# SpiderHand.net
KiCad netlist of a schematic drawn in EAGLE
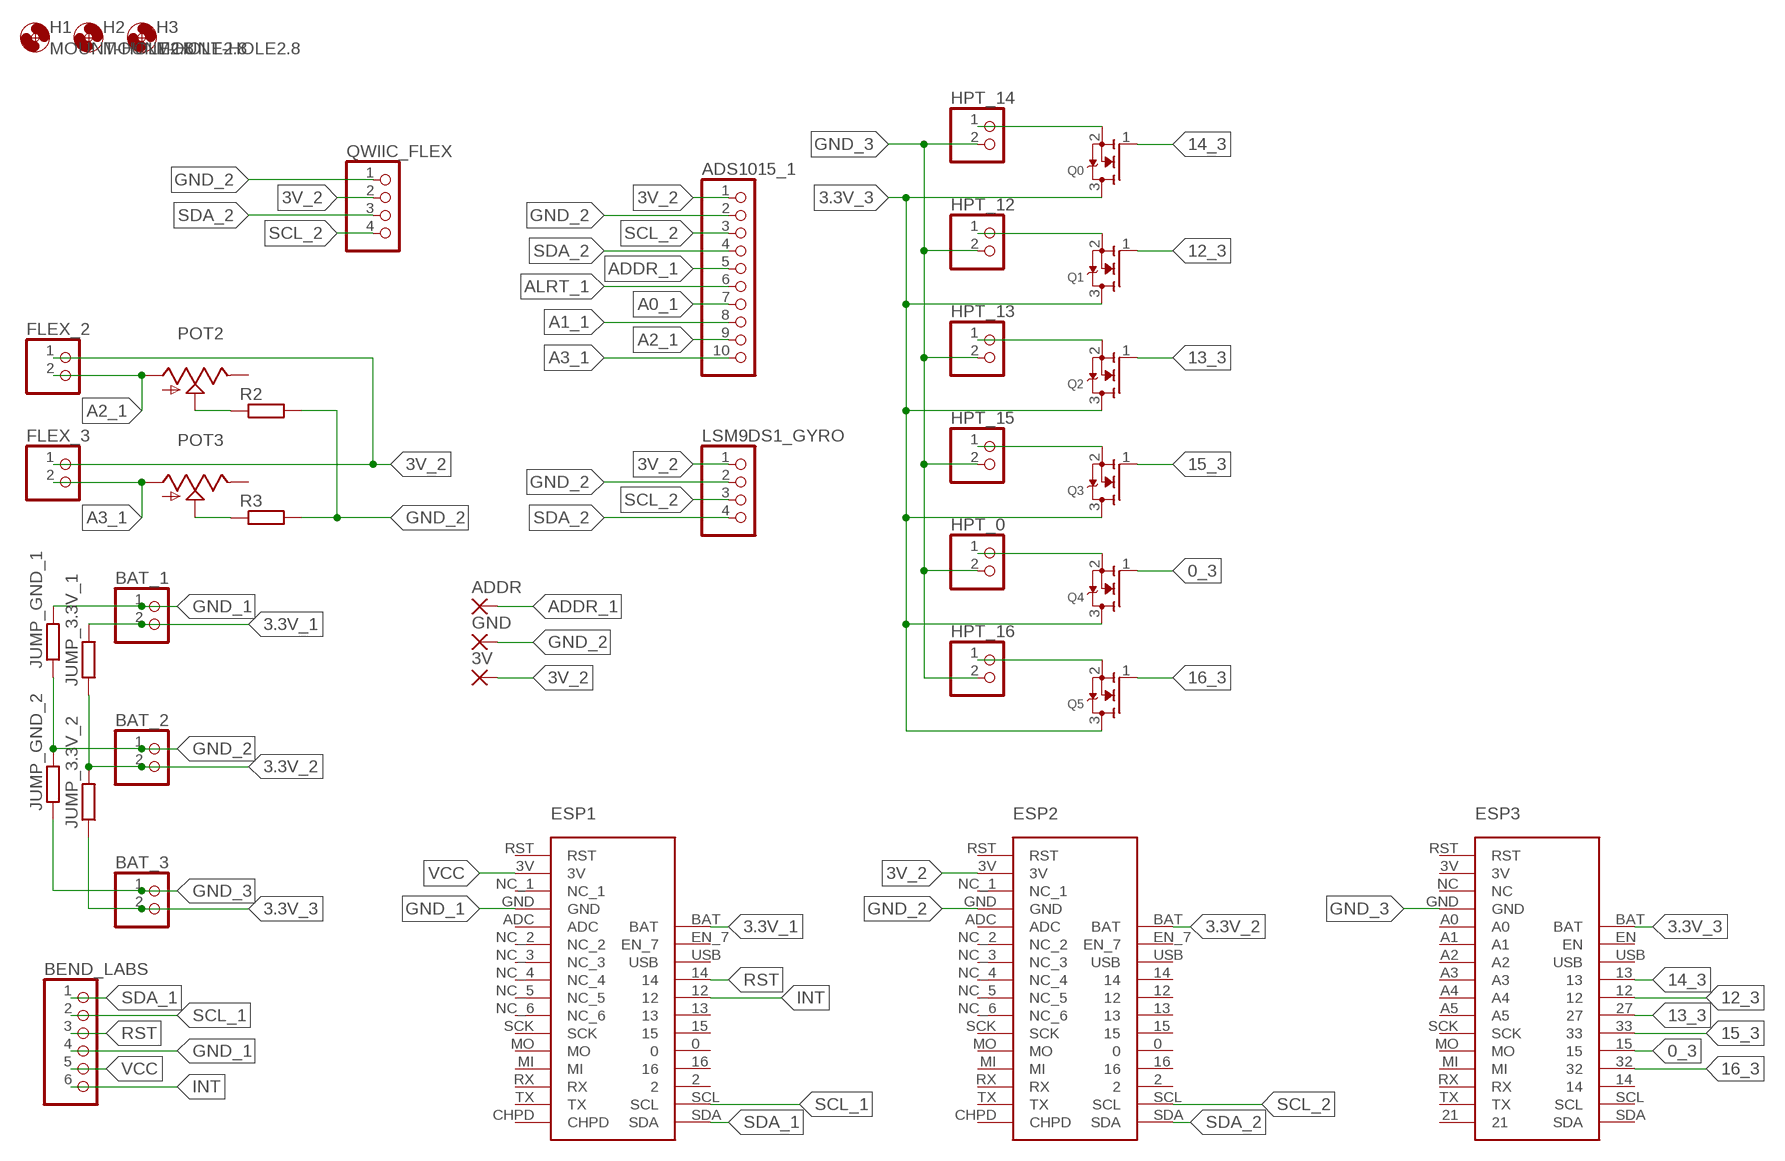
[diagram p0: schematic, sheet 1]

(export (version "E")
  (design (tool "Eeschema 10.0.6"))
  (components
    (comp (ref "3V")
      (value "SMD2")
      (footprint "eagle-import:SMD1,27-2,54")
      (libsource (lib "eagle-import") (part "SMD2"))
    )
    (comp (ref "ADDR")
      (value "SMD2")
      (footprint "eagle-import:SMD1,27-2,54")
      (libsource (lib "eagle-import") (part "SMD2"))
    )
    (comp (ref "ADS1015_1")
      (value "PINHD-1X10")
      (footprint "eagle-import:1X10")
      (libsource (lib "eagle-import") (part "PINHD-1X10"))
    )
    (comp (ref "BAT_1")
      (value "PINHD-1X2")
      (footprint "eagle-import:1X02")
      (libsource (lib "eagle-import") (part "PINHD-1X2"))
    )
    (comp (ref "BAT_2")
      (value "PINHD-1X2")
      (footprint "eagle-import:1X02")
      (libsource (lib "eagle-import") (part "PINHD-1X2"))
    )
    (comp (ref "BAT_3")
      (value "PINHD-1X2")
      (footprint "eagle-import:1X02")
      (fields (field (name "SPICEPREFIX") "B"))
      (libsource (lib "eagle-import") (part "PINHD-1X2"))
    )
    (comp (ref "BEND_LABS")
      (value "PINHD-1X6/90")
      (footprint "eagle-import:1X06_90")
      (libsource (lib "eagle-import") (part "PINHD-1X6/90"))
    )
    (comp (ref "ESP1")
      (value "ESP_8266_ADAFRUIT")
      (footprint "eagle-import:ESP_8266_ADAFRUIT")
      (libsource (lib "eagle-import") (part "ESP_8266_ADAFRUIT"))
    )
    (comp (ref "ESP2")
      (value "ESP_8266_ADAFRUIT")
      (footprint "eagle-import:ESP_8266_ADAFRUIT")
      (libsource (lib "eagle-import") (part "ESP_8266_ADAFRUIT"))
    )
    (comp (ref "ESP3")
      (value "ESP_32_ADAFRUIT")
      (footprint "eagle-import:ESP_32_ADAFRUIT")
      (libsource (lib "eagle-import") (part "ESP_32_ADAFRUIT"))
    )
    (comp (ref "FLEX_2")
      (value "PINHD-1X2")
      (footprint "eagle-import:1X02")
      (libsource (lib "eagle-import") (part "PINHD-1X2"))
    )
    (comp (ref "FLEX_3")
      (value "PINHD-1X2")
      (footprint "eagle-import:1X02")
      (libsource (lib "eagle-import") (part "PINHD-1X2"))
    )
    (comp (ref "GND")
      (value "SMD2")
      (footprint "eagle-import:SMD1,27-2,54")
      (libsource (lib "eagle-import") (part "SMD2"))
    )
    (comp (ref "H1")
      (value "MOUNT-HOLE2.8")
      (footprint "eagle-import:2,8")
      (libsource (lib "eagle-import") (part "MOUNT-HOLE2.8"))
    )
    (comp (ref "H2")
      (value "MOUNT-HOLE2.8")
      (footprint "eagle-import:2,8")
      (libsource (lib "eagle-import") (part "MOUNT-HOLE2.8"))
    )
    (comp (ref "H3")
      (value "MOUNT-HOLE2.8")
      (footprint "eagle-import:2,8")
      (libsource (lib "eagle-import") (part "MOUNT-HOLE2.8"))
    )
    (comp (ref "HPT_0")
      (value "PINHD-1X2")
      (footprint "eagle-import:1X02")
      (libsource (lib "eagle-import") (part "PINHD-1X2"))
    )
    (comp (ref "HPT_12")
      (value "PINHD-1X2")
      (footprint "eagle-import:1X02")
      (libsource (lib "eagle-import") (part "PINHD-1X2"))
    )
    (comp (ref "HPT_13")
      (value "PINHD-1X2")
      (footprint "eagle-import:1X02")
      (libsource (lib "eagle-import") (part "PINHD-1X2"))
    )
    (comp (ref "HPT_14")
      (value "PINHD-1X2")
      (footprint "eagle-import:1X02")
      (libsource (lib "eagle-import") (part "PINHD-1X2"))
    )
    (comp (ref "HPT_15")
      (value "PINHD-1X2")
      (footprint "eagle-import:1X02")
      (libsource (lib "eagle-import") (part "PINHD-1X2"))
    )
    (comp (ref "HPT_16")
      (value "PINHD-1X2")
      (footprint "eagle-import:1X02")
      (libsource (lib "eagle-import") (part "PINHD-1X2"))
    )
    (comp (ref "JUMP_3.3V_1")
      (value "R-EU_M0805")
      (footprint "eagle-import:M0805")
      (libsource (lib "eagle-import") (part "R-EU_M0805"))
    )
    (comp (ref "JUMP_3.3V_2")
      (value "R-EU_M0805")
      (footprint "eagle-import:M0805")
      (libsource (lib "eagle-import") (part "R-EU_M0805"))
    )
    (comp (ref "JUMP_GND_1")
      (value "R-EU_M0805")
      (footprint "eagle-import:M0805")
      (libsource (lib "eagle-import") (part "R-EU_M0805"))
    )
    (comp (ref "JUMP_GND_2")
      (value "R-EU_M0805")
      (footprint "eagle-import:M0805")
      (libsource (lib "eagle-import") (part "R-EU_M0805"))
    )
    (comp (ref "LSM9DS1_GYRO")
      (value "PINHD-1X4/90")
      (footprint "eagle-import:1X04_90")
      (libsource (lib "eagle-import") (part "PINHD-1X4/90"))
    )
    (comp (ref "POT2")
      (value "TRIM_US-CA6V")
      (footprint "eagle-import:CA6V")
      (libsource (lib "eagle-import") (part "TRIM_US-CA6V"))
    )
    (comp (ref "POT3")
      (value "TRIM_US-CA6V")
      (footprint "eagle-import:CA6V")
      (libsource (lib "eagle-import") (part "TRIM_US-CA6V"))
    )
    (comp (ref "Q0")
      (value "MOSFET-NREFLOW")
      (footprint "eagle-import:SOT23")
      (libsource (lib "eagle-import") (part "MOSFET-NREFLOW"))
    )
    (comp (ref "Q1")
      (value "MOSFET-NREFLOW")
      (footprint "eagle-import:SOT23")
      (libsource (lib "eagle-import") (part "MOSFET-NREFLOW"))
    )
    (comp (ref "Q2")
      (value "MOSFET-NREFLOW")
      (footprint "eagle-import:SOT23")
      (libsource (lib "eagle-import") (part "MOSFET-NREFLOW"))
    )
    (comp (ref "Q3")
      (value "MOSFET-NREFLOW")
      (footprint "eagle-import:SOT23")
      (libsource (lib "eagle-import") (part "MOSFET-NREFLOW"))
    )
    (comp (ref "Q4")
      (value "MOSFET-NREFLOW")
      (footprint "eagle-import:SOT23")
      (libsource (lib "eagle-import") (part "MOSFET-NREFLOW"))
    )
    (comp (ref "Q5")
      (value "MOSFET-NREFLOW")
      (footprint "eagle-import:SOT23")
      (libsource (lib "eagle-import") (part "MOSFET-NREFLOW"))
    )
    (comp (ref "QWIIC_FLEX")
      (value "PINHD-1X4/90")
      (footprint "eagle-import:1X04_90")
      (libsource (lib "eagle-import") (part "PINHD-1X4/90"))
    )
    (comp (ref "R2")
      (value "R-EU_0204/7")
      (footprint "eagle-import:0204_7")
      (libsource (lib "eagle-import") (part "R-EU_0204/7"))
    )
    (comp (ref "R3")
      (value "R-EU_0204/7")
      (footprint "eagle-import:0204_7")
      (libsource (lib "eagle-import") (part "R-EU_0204/7"))
    )
  )
  (nets
    (net (code "1") (name "0_3") (class "Default")
      (node (ref "ESP3") (pin "15") (pinfunction "15_15") (pintype "bidirectional"))
      (node (ref "Q4") (pin "1") (pinfunction "G_1") (pintype "bidirectional"))
    )
    (net (code "2") (name "3.3V_1") (class "Default")
      (node (ref "BAT_1") (pin "2") (pinfunction "2_2") (pintype "passive"))
      (node (ref "ESP1") (pin "BAT") (pinfunction "BAT_BAT") (pintype "bidirectional"))
      (node (ref "JUMP_3.3V_1") (pin "2") (pinfunction "2_2") (pintype "passive"))
    )
    (net (code "3") (name "3.3V_2") (class "Default")
      (node (ref "BAT_2") (pin "2") (pinfunction "2_2") (pintype "passive"))
      (node (ref "ESP2") (pin "BAT") (pinfunction "BAT_BAT") (pintype "bidirectional"))
      (node (ref "JUMP_3.3V_1") (pin "1") (pinfunction "1_1") (pintype "passive"))
      (node (ref "JUMP_3.3V_2") (pin "2") (pinfunction "2_2") (pintype "passive"))
    )
    (net (code "4") (name "3.3V_3") (class "Default")
      (node (ref "BAT_3") (pin "2") (pinfunction "2_2") (pintype "passive"))
      (node (ref "ESP3") (pin "BAT") (pinfunction "BAT_BAT") (pintype "bidirectional"))
      (node (ref "JUMP_3.3V_2") (pin "1") (pinfunction "1_1") (pintype "passive"))
      (node (ref "Q0") (pin "3") (pinfunction "D_3") (pintype "bidirectional"))
      (node (ref "Q1") (pin "3") (pinfunction "D_3") (pintype "bidirectional"))
      (node (ref "Q2") (pin "3") (pinfunction "D_3") (pintype "bidirectional"))
      (node (ref "Q3") (pin "3") (pinfunction "D_3") (pintype "bidirectional"))
      (node (ref "Q4") (pin "3") (pinfunction "D_3") (pintype "bidirectional"))
      (node (ref "Q5") (pin "3") (pinfunction "D_3") (pintype "bidirectional"))
    )
    (net (code "5") (name "3V_2") (class "Default")
      (node (ref "3V") (pin "1") (pinfunction "P_1") (pintype "passive"))
      (node (ref "ADS1015_1") (pin "1") (pinfunction "1_1") (pintype "passive"))
      (node (ref "ESP2") (pin "3V") (pinfunction "3V_3V") (pintype "bidirectional"))
      (node (ref "FLEX_2") (pin "1") (pinfunction "1_1") (pintype "passive"))
      (node (ref "FLEX_3") (pin "1") (pinfunction "1_1") (pintype "passive"))
      (node (ref "LSM9DS1_GYRO") (pin "1") (pinfunction "1_1") (pintype "passive"))
      (node (ref "QWIIC_FLEX") (pin "2") (pinfunction "2_2") (pintype "passive"))
    )
    (net (code "6") (name "12_3") (class "Default")
      (node (ref "ESP3") (pin "12") (pinfunction "12_12") (pintype "bidirectional"))
      (node (ref "Q1") (pin "1") (pinfunction "G_1") (pintype "bidirectional"))
    )
    (net (code "7") (name "13_3") (class "Default")
      (node (ref "ESP3") (pin "27") (pinfunction "27_27") (pintype "bidirectional"))
      (node (ref "Q2") (pin "1") (pinfunction "G_1") (pintype "bidirectional"))
    )
    (net (code "8") (name "14_3") (class "Default")
      (node (ref "ESP3") (pin "13") (pinfunction "13_13") (pintype "bidirectional"))
      (node (ref "Q0") (pin "1") (pinfunction "G_1") (pintype "bidirectional"))
    )
    (net (code "9") (name "15_3") (class "Default")
      (node (ref "ESP3") (pin "33") (pinfunction "33_33") (pintype "bidirectional"))
      (node (ref "Q3") (pin "1") (pinfunction "G_1") (pintype "bidirectional"))
    )
    (net (code "10") (name "16_3") (class "Default")
      (node (ref "ESP3") (pin "32") (pinfunction "32_32") (pintype "bidirectional"))
      (node (ref "Q5") (pin "1") (pinfunction "G_1") (pintype "bidirectional"))
    )
    (net (code "11") (name "A0_1") (class "Default")
      (node (ref "ADS1015_1") (pin "7") (pinfunction "7_7") (pintype "passive"))
    )
    (net (code "12") (name "A1_1") (class "Default")
      (node (ref "ADS1015_1") (pin "8") (pinfunction "8_8") (pintype "passive"))
    )
    (net (code "13") (name "A2_1") (class "Default")
      (node (ref "ADS1015_1") (pin "9") (pinfunction "9_9") (pintype "passive"))
      (node (ref "FLEX_2") (pin "2") (pinfunction "2_2") (pintype "passive"))
      (node (ref "POT2") (pin "A") (pinfunction "A_A") (pintype "passive"))
    )
    (net (code "14") (name "A3_1") (class "Default")
      (node (ref "ADS1015_1") (pin "10") (pinfunction "10_10") (pintype "passive"))
      (node (ref "FLEX_3") (pin "2") (pinfunction "2_2") (pintype "passive"))
      (node (ref "POT3") (pin "A") (pinfunction "A_A") (pintype "passive"))
    )
    (net (code "15") (name "ADDR_1") (class "Default")
      (node (ref "ADDR") (pin "1") (pinfunction "P_1") (pintype "passive"))
      (node (ref "ADS1015_1") (pin "5") (pinfunction "5_5") (pintype "passive"))
    )
    (net (code "16") (name "ALRT_1") (class "Default")
      (node (ref "ADS1015_1") (pin "6") (pinfunction "6_6") (pintype "passive"))
    )
    (net (code "17") (name "GND_1") (class "Default")
      (node (ref "BAT_1") (pin "1") (pinfunction "1_1") (pintype "passive"))
      (node (ref "BEND_LABS") (pin "4") (pinfunction "4_4") (pintype "passive"))
      (node (ref "ESP1") (pin "GND") (pinfunction "GND_GND") (pintype "bidirectional"))
      (node (ref "JUMP_GND_1") (pin "2") (pinfunction "2_2") (pintype "passive"))
    )
    (net (code "18") (name "GND_2") (class "Default")
      (node (ref "ADS1015_1") (pin "2") (pinfunction "2_2") (pintype "passive"))
      (node (ref "BAT_2") (pin "1") (pinfunction "1_1") (pintype "passive"))
      (node (ref "ESP2") (pin "GND") (pinfunction "GND_GND") (pintype "bidirectional"))
      (node (ref "GND") (pin "1") (pinfunction "P_1") (pintype "passive"))
      (node (ref "JUMP_GND_1") (pin "1") (pinfunction "1_1") (pintype "passive"))
      (node (ref "JUMP_GND_2") (pin "2") (pinfunction "2_2") (pintype "passive"))
      (node (ref "LSM9DS1_GYRO") (pin "2") (pinfunction "2_2") (pintype "passive"))
      (node (ref "QWIIC_FLEX") (pin "1") (pinfunction "1_1") (pintype "passive"))
      (node (ref "R2") (pin "2") (pinfunction "2_2") (pintype "passive"))
      (node (ref "R3") (pin "2") (pinfunction "2_2") (pintype "passive"))
    )
    (net (code "19") (name "GND_3") (class "Default")
      (node (ref "BAT_3") (pin "1") (pinfunction "1_1") (pintype "passive"))
      (node (ref "ESP3") (pin "GND") (pinfunction "GND_GND") (pintype "bidirectional"))
      (node (ref "HPT_0") (pin "2") (pinfunction "2_2") (pintype "passive"))
      (node (ref "HPT_12") (pin "2") (pinfunction "2_2") (pintype "passive"))
      (node (ref "HPT_13") (pin "2") (pinfunction "2_2") (pintype "passive"))
      (node (ref "HPT_14") (pin "2") (pinfunction "2_2") (pintype "passive"))
      (node (ref "HPT_15") (pin "2") (pinfunction "2_2") (pintype "passive"))
      (node (ref "HPT_16") (pin "2") (pinfunction "2_2") (pintype "passive"))
      (node (ref "JUMP_GND_2") (pin "1") (pinfunction "1_1") (pintype "passive"))
    )
    (net (code "20") (name "INT") (class "Default")
      (node (ref "BEND_LABS") (pin "6") (pinfunction "6_6") (pintype "passive"))
      (node (ref "ESP1") (pin "12") (pinfunction "12_12") (pintype "bidirectional"))
    )
    (net (code "21") (name "Net-(POT2-PadS)") (class "Default")
      (node (ref "POT2") (pin "S") (pinfunction "S_S") (pintype "passive"))
      (node (ref "R2") (pin "1") (pinfunction "1_1") (pintype "passive"))
    )
    (net (code "22") (name "Net-(POT3-PadS)") (class "Default")
      (node (ref "POT3") (pin "S") (pinfunction "S_S") (pintype "passive"))
      (node (ref "R3") (pin "1") (pinfunction "1_1") (pintype "passive"))
    )
    (net (code "23") (name "Net-(Q0-S)") (class "Default")
      (node (ref "HPT_14") (pin "1") (pinfunction "1_1") (pintype "passive"))
      (node (ref "Q0") (pin "2") (pinfunction "S_2") (pintype "bidirectional"))
    )
    (net (code "24") (name "Net-(Q1-S)") (class "Default")
      (node (ref "HPT_12") (pin "1") (pinfunction "1_1") (pintype "passive"))
      (node (ref "Q1") (pin "2") (pinfunction "S_2") (pintype "bidirectional"))
    )
    (net (code "25") (name "Net-(Q2-S)") (class "Default")
      (node (ref "HPT_13") (pin "1") (pinfunction "1_1") (pintype "passive"))
      (node (ref "Q2") (pin "2") (pinfunction "S_2") (pintype "bidirectional"))
    )
    (net (code "26") (name "Net-(Q3-S)") (class "Default")
      (node (ref "HPT_15") (pin "1") (pinfunction "1_1") (pintype "passive"))
      (node (ref "Q3") (pin "2") (pinfunction "S_2") (pintype "bidirectional"))
    )
    (net (code "27") (name "Net-(Q4-S)") (class "Default")
      (node (ref "HPT_0") (pin "1") (pinfunction "1_1") (pintype "passive"))
      (node (ref "Q4") (pin "2") (pinfunction "S_2") (pintype "bidirectional"))
    )
    (net (code "28") (name "Net-(Q5-S)") (class "Default")
      (node (ref "HPT_16") (pin "1") (pinfunction "1_1") (pintype "passive"))
      (node (ref "Q5") (pin "2") (pinfunction "S_2") (pintype "bidirectional"))
    )
    (net (code "29") (name "RST") (class "Default")
      (node (ref "BEND_LABS") (pin "3") (pinfunction "3_3") (pintype "passive"))
      (node (ref "ESP1") (pin "14") (pinfunction "14_14") (pintype "bidirectional"))
    )
    (net (code "30") (name "SCL_1") (class "Default")
      (node (ref "BEND_LABS") (pin "2") (pinfunction "2_2") (pintype "passive"))
      (node (ref "ESP1") (pin "SCL") (pinfunction "SCL_SCL") (pintype "bidirectional"))
    )
    (net (code "31") (name "SCL_2") (class "Default")
      (node (ref "ADS1015_1") (pin "3") (pinfunction "3_3") (pintype "passive"))
      (node (ref "ESP2") (pin "SCL") (pinfunction "SCL_SCL") (pintype "bidirectional"))
      (node (ref "LSM9DS1_GYRO") (pin "3") (pinfunction "3_3") (pintype "passive"))
      (node (ref "QWIIC_FLEX") (pin "4") (pinfunction "4_4") (pintype "passive"))
    )
    (net (code "32") (name "SDA_1") (class "Default")
      (node (ref "BEND_LABS") (pin "1") (pinfunction "1_1") (pintype "passive"))
      (node (ref "ESP1") (pin "SDA") (pinfunction "SDA_SDA") (pintype "bidirectional"))
    )
    (net (code "33") (name "SDA_2") (class "Default")
      (node (ref "ADS1015_1") (pin "4") (pinfunction "4_4") (pintype "passive"))
      (node (ref "ESP2") (pin "SDA") (pinfunction "SDA_SDA") (pintype "bidirectional"))
      (node (ref "LSM9DS1_GYRO") (pin "4") (pinfunction "4_4") (pintype "passive"))
      (node (ref "QWIIC_FLEX") (pin "3") (pinfunction "3_3") (pintype "passive"))
    )
    (net (code "34") (name "VCC") (class "Default")
      (node (ref "BEND_LABS") (pin "5") (pinfunction "5_5") (pintype "passive"))
      (node (ref "ESP1") (pin "3V") (pinfunction "3V_3V") (pintype "bidirectional"))
    )
    (net (code "35") (name "unconnected-(ESP1-Pad0)") (class "Default")
      (node (ref "ESP1") (pin "0") (pinfunction "0_0") (pintype "bidirectional"))
    )
    (net (code "36") (name "unconnected-(ESP1-Pad2)") (class "Default")
      (node (ref "ESP1") (pin "2") (pinfunction "2_2") (pintype "bidirectional"))
    )
    (net (code "37") (name "unconnected-(ESP1-Pad13)") (class "Default")
      (node (ref "ESP1") (pin "13") (pinfunction "13_13") (pintype "bidirectional"))
    )
    (net (code "38") (name "unconnected-(ESP1-Pad15)") (class "Default")
      (node (ref "ESP1") (pin "15") (pinfunction "15_15") (pintype "bidirectional"))
    )
    (net (code "39") (name "unconnected-(ESP1-Pad16)") (class "Default")
      (node (ref "ESP1") (pin "16") (pinfunction "16_16") (pintype "bidirectional"))
    )
    (net (code "40") (name "unconnected-(ESP1-PadADC)") (class "Default")
      (node (ref "ESP1") (pin "ADC") (pinfunction "ADC_ADC") (pintype "bidirectional"))
    )
    (net (code "41") (name "unconnected-(ESP1-PadCHPD)") (class "Default")
      (node (ref "ESP1") (pin "CHPD") (pinfunction "CHPD_CHPD") (pintype "bidirectional"))
    )
    (net (code "42") (name "unconnected-(ESP1-PadEN_7)") (class "Default")
      (node (ref "ESP1") (pin "EN_7") (pinfunction "EN_7_EN_7") (pintype "bidirectional"))
    )
    (net (code "43") (name "unconnected-(ESP1-PadMI)") (class "Default")
      (node (ref "ESP1") (pin "MI") (pinfunction "MI_MI") (pintype "bidirectional"))
    )
    (net (code "44") (name "unconnected-(ESP1-PadMO)") (class "Default")
      (node (ref "ESP1") (pin "MO") (pinfunction "MO_MO") (pintype "bidirectional"))
    )
    (net (code "45") (name "unconnected-(ESP1-PadNC_1)") (class "Default")
      (node (ref "ESP1") (pin "NC_1") (pinfunction "NC_1_NC_1") (pintype "bidirectional"))
    )
    (net (code "46") (name "unconnected-(ESP1-PadNC_2)") (class "Default")
      (node (ref "ESP1") (pin "NC_2") (pinfunction "NC_2_NC_2") (pintype "bidirectional"))
    )
    (net (code "47") (name "unconnected-(ESP1-PadNC_3)") (class "Default")
      (node (ref "ESP1") (pin "NC_3") (pinfunction "NC_3_NC_3") (pintype "bidirectional"))
    )
    (net (code "48") (name "unconnected-(ESP1-PadNC_4)") (class "Default")
      (node (ref "ESP1") (pin "NC_4") (pinfunction "NC_4_NC_4") (pintype "bidirectional"))
    )
    (net (code "49") (name "unconnected-(ESP1-PadNC_5)") (class "Default")
      (node (ref "ESP1") (pin "NC_5") (pinfunction "NC_5_NC_5") (pintype "bidirectional"))
    )
    (net (code "50") (name "unconnected-(ESP1-PadNC_6)") (class "Default")
      (node (ref "ESP1") (pin "NC_6") (pinfunction "NC_6_NC_6") (pintype "bidirectional"))
    )
    (net (code "51") (name "unconnected-(ESP1-PadRST)") (class "Default")
      (node (ref "ESP1") (pin "RST") (pinfunction "RST_RST") (pintype "bidirectional"))
    )
    (net (code "52") (name "unconnected-(ESP1-PadRX)") (class "Default")
      (node (ref "ESP1") (pin "RX") (pinfunction "RX_RX") (pintype "bidirectional"))
    )
    (net (code "53") (name "unconnected-(ESP1-PadSCK)") (class "Default")
      (node (ref "ESP1") (pin "SCK") (pinfunction "SCK_SCK") (pintype "bidirectional"))
    )
    (net (code "54") (name "unconnected-(ESP1-PadTX)") (class "Default")
      (node (ref "ESP1") (pin "TX") (pinfunction "TX_TX") (pintype "bidirectional"))
    )
    (net (code "55") (name "unconnected-(ESP1-PadUSB)") (class "Default")
      (node (ref "ESP1") (pin "USB") (pinfunction "USB_USB") (pintype "bidirectional"))
    )
    (net (code "56") (name "unconnected-(ESP2-Pad0)") (class "Default")
      (node (ref "ESP2") (pin "0") (pinfunction "0_0") (pintype "bidirectional"))
    )
    (net (code "57") (name "unconnected-(ESP2-Pad2)") (class "Default")
      (node (ref "ESP2") (pin "2") (pinfunction "2_2") (pintype "bidirectional"))
    )
    (net (code "58") (name "unconnected-(ESP2-Pad12)") (class "Default")
      (node (ref "ESP2") (pin "12") (pinfunction "12_12") (pintype "bidirectional"))
    )
    (net (code "59") (name "unconnected-(ESP2-Pad13)") (class "Default")
      (node (ref "ESP2") (pin "13") (pinfunction "13_13") (pintype "bidirectional"))
    )
    (net (code "60") (name "unconnected-(ESP2-Pad14)") (class "Default")
      (node (ref "ESP2") (pin "14") (pinfunction "14_14") (pintype "bidirectional"))
    )
    (net (code "61") (name "unconnected-(ESP2-Pad15)") (class "Default")
      (node (ref "ESP2") (pin "15") (pinfunction "15_15") (pintype "bidirectional"))
    )
    (net (code "62") (name "unconnected-(ESP2-Pad16)") (class "Default")
      (node (ref "ESP2") (pin "16") (pinfunction "16_16") (pintype "bidirectional"))
    )
    (net (code "63") (name "unconnected-(ESP2-PadADC)") (class "Default")
      (node (ref "ESP2") (pin "ADC") (pinfunction "ADC_ADC") (pintype "bidirectional"))
    )
    (net (code "64") (name "unconnected-(ESP2-PadCHPD)") (class "Default")
      (node (ref "ESP2") (pin "CHPD") (pinfunction "CHPD_CHPD") (pintype "bidirectional"))
    )
    (net (code "65") (name "unconnected-(ESP2-PadEN_7)") (class "Default")
      (node (ref "ESP2") (pin "EN_7") (pinfunction "EN_7_EN_7") (pintype "bidirectional"))
    )
    (net (code "66") (name "unconnected-(ESP2-PadMI)") (class "Default")
      (node (ref "ESP2") (pin "MI") (pinfunction "MI_MI") (pintype "bidirectional"))
    )
    (net (code "67") (name "unconnected-(ESP2-PadMO)") (class "Default")
      (node (ref "ESP2") (pin "MO") (pinfunction "MO_MO") (pintype "bidirectional"))
    )
    (net (code "68") (name "unconnected-(ESP2-PadNC_1)") (class "Default")
      (node (ref "ESP2") (pin "NC_1") (pinfunction "NC_1_NC_1") (pintype "bidirectional"))
    )
    (net (code "69") (name "unconnected-(ESP2-PadNC_2)") (class "Default")
      (node (ref "ESP2") (pin "NC_2") (pinfunction "NC_2_NC_2") (pintype "bidirectional"))
    )
    (net (code "70") (name "unconnected-(ESP2-PadNC_3)") (class "Default")
      (node (ref "ESP2") (pin "NC_3") (pinfunction "NC_3_NC_3") (pintype "bidirectional"))
    )
    (net (code "71") (name "unconnected-(ESP2-PadNC_4)") (class "Default")
      (node (ref "ESP2") (pin "NC_4") (pinfunction "NC_4_NC_4") (pintype "bidirectional"))
    )
    (net (code "72") (name "unconnected-(ESP2-PadNC_5)") (class "Default")
      (node (ref "ESP2") (pin "NC_5") (pinfunction "NC_5_NC_5") (pintype "bidirectional"))
    )
    (net (code "73") (name "unconnected-(ESP2-PadNC_6)") (class "Default")
      (node (ref "ESP2") (pin "NC_6") (pinfunction "NC_6_NC_6") (pintype "bidirectional"))
    )
    (net (code "74") (name "unconnected-(ESP2-PadRST)") (class "Default")
      (node (ref "ESP2") (pin "RST") (pinfunction "RST_RST") (pintype "bidirectional"))
    )
    (net (code "75") (name "unconnected-(ESP2-PadRX)") (class "Default")
      (node (ref "ESP2") (pin "RX") (pinfunction "RX_RX") (pintype "bidirectional"))
    )
    (net (code "76") (name "unconnected-(ESP2-PadSCK)") (class "Default")
      (node (ref "ESP2") (pin "SCK") (pinfunction "SCK_SCK") (pintype "bidirectional"))
    )
    (net (code "77") (name "unconnected-(ESP2-PadTX)") (class "Default")
      (node (ref "ESP2") (pin "TX") (pinfunction "TX_TX") (pintype "bidirectional"))
    )
    (net (code "78") (name "unconnected-(ESP2-PadUSB)") (class "Default")
      (node (ref "ESP2") (pin "USB") (pinfunction "USB_USB") (pintype "bidirectional"))
    )
    (net (code "79") (name "unconnected-(ESP3-Pad3V)") (class "Default")
      (node (ref "ESP3") (pin "3V") (pinfunction "3V_3V") (pintype "bidirectional"))
    )
    (net (code "80") (name "unconnected-(ESP3-Pad14)") (class "Default")
      (node (ref "ESP3") (pin "14") (pinfunction "14_14") (pintype "bidirectional"))
    )
    (net (code "81") (name "unconnected-(ESP3-Pad21)") (class "Default")
      (node (ref "ESP3") (pin "21") (pinfunction "21_21") (pintype "bidirectional"))
    )
    (net (code "82") (name "unconnected-(ESP3-PadA0)") (class "Default")
      (node (ref "ESP3") (pin "A0") (pinfunction "A0_A0") (pintype "bidirectional"))
    )
    (net (code "83") (name "unconnected-(ESP3-PadA1)") (class "Default")
      (node (ref "ESP3") (pin "A1") (pinfunction "A1_A1") (pintype "bidirectional"))
    )
    (net (code "84") (name "unconnected-(ESP3-PadA2)") (class "Default")
      (node (ref "ESP3") (pin "A2") (pinfunction "A2_A2") (pintype "bidirectional"))
    )
    (net (code "85") (name "unconnected-(ESP3-PadA3)") (class "Default")
      (node (ref "ESP3") (pin "A3") (pinfunction "A3_A3") (pintype "bidirectional"))
    )
    (net (code "86") (name "unconnected-(ESP3-PadA4)") (class "Default")
      (node (ref "ESP3") (pin "A4") (pinfunction "A4_A4") (pintype "bidirectional"))
    )
    (net (code "87") (name "unconnected-(ESP3-PadA5)") (class "Default")
      (node (ref "ESP3") (pin "A5") (pinfunction "A5_A5") (pintype "bidirectional"))
    )
    (net (code "88") (name "unconnected-(ESP3-PadEN)") (class "Default")
      (node (ref "ESP3") (pin "EN") (pinfunction "EN_EN") (pintype "bidirectional"))
    )
    (net (code "89") (name "unconnected-(ESP3-PadMI)") (class "Default")
      (node (ref "ESP3") (pin "MI") (pinfunction "MI_MI") (pintype "bidirectional"))
    )
    (net (code "90") (name "unconnected-(ESP3-PadMO)") (class "Default")
      (node (ref "ESP3") (pin "MO") (pinfunction "MO_MO") (pintype "bidirectional"))
    )
    (net (code "91") (name "unconnected-(ESP3-PadNC)") (class "Default")
      (node (ref "ESP3") (pin "NC") (pinfunction "NC_NC") (pintype "bidirectional"))
    )
    (net (code "92") (name "unconnected-(ESP3-PadRST)") (class "Default")
      (node (ref "ESP3") (pin "RST") (pinfunction "RST_RST") (pintype "bidirectional"))
    )
    (net (code "93") (name "unconnected-(ESP3-PadRX)") (class "Default")
      (node (ref "ESP3") (pin "RX") (pinfunction "RX_RX") (pintype "bidirectional"))
    )
    (net (code "94") (name "unconnected-(ESP3-PadSCK)") (class "Default")
      (node (ref "ESP3") (pin "SCK") (pinfunction "SCK_SCK") (pintype "bidirectional"))
    )
    (net (code "95") (name "unconnected-(ESP3-PadSCL)") (class "Default")
      (node (ref "ESP3") (pin "SCL") (pinfunction "SCL_SCL") (pintype "bidirectional"))
    )
    (net (code "96") (name "unconnected-(ESP3-PadSDA)") (class "Default")
      (node (ref "ESP3") (pin "SDA") (pinfunction "SDA_SDA") (pintype "bidirectional"))
    )
    (net (code "97") (name "unconnected-(ESP3-PadTX)") (class "Default")
      (node (ref "ESP3") (pin "TX") (pinfunction "TX_TX") (pintype "bidirectional"))
    )
    (net (code "98") (name "unconnected-(ESP3-PadUSB)") (class "Default")
      (node (ref "ESP3") (pin "USB") (pinfunction "USB_USB") (pintype "bidirectional"))
    )
    (net (code "99") (name "unconnected-(POT2-PadE)") (class "Default")
      (node (ref "POT2") (pin "E") (pinfunction "E_E") (pintype "passive"))
    )
    (net (code "100") (name "unconnected-(POT3-PadE)") (class "Default")
      (node (ref "POT3") (pin "E") (pinfunction "E_E") (pintype "passive"))
    )
  )
)
